# Puzzle_-_Temperature_Sensor_Analog_v1_0.net
KiCad netlist of a schematic drawn in EAGLE
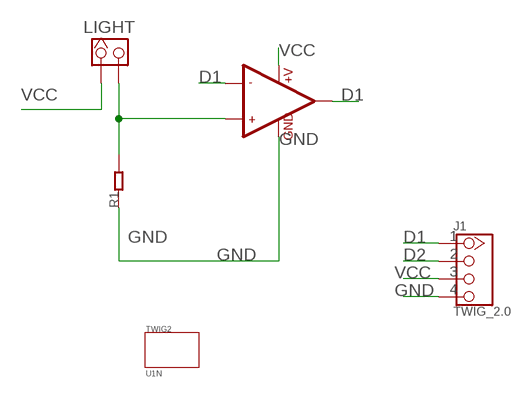
[diagram p0: schematic, sheet 1]

(export (version "E")
  (design (tool "Eeschema 10.0.6"))
  (components
    (comp (ref "J1")
      (value "TWIG_2.0")
      (footprint "eagle-import:2.0_1X4")
      (libsource (lib "eagle-import") (part "TWIG_2.0F''"))
    )
    (comp (ref "LIGHT")
      (value "HEADER_1X2_2.54")
      (footprint "eagle-import:CK_1_2")
      (libsource (lib "eagle-import") (part "HEADER_1X2_2.54"))
    )
    (comp (ref "R1")
      (value "R0603")
      (footprint "eagle-import:0603")
      (libsource (lib "eagle-import") (part "R0603"))
    )
    (comp (ref "TWIG2")
      (value "U1N")
      (footprint "eagle-import:U1N")
      (libsource (lib "eagle-import") (part "U1N"))
    )
    (comp (ref "U1")
      (value "LMV358")
      (footprint "eagle-import:SO08")
      (libsource (lib "eagle-import") (part "LMV358"))
    )
  )
  (nets
    (net (code "1") (name "/D1") (class "Default")
      (node (ref "J1") (pin "1") (pinfunction "1_1") (pintype "bidirectional"))
      (node (ref "U1") (pin "1") (pinfunction "OUT1_1") (pintype "output"))
      (node (ref "U1") (pin "2") (pinfunction "-IN1_2") (pintype "input"))
    )
    (net (code "2") (name "/D2") (class "Default")
      (node (ref "J1") (pin "2") (pinfunction "2_2") (pintype "bidirectional"))
    )
    (net (code "3") (name "/GND") (class "Default")
      (node (ref "J1") (pin "4") (pinfunction "4_4") (pintype "bidirectional"))
      (node (ref "R1") (pin "1") (pinfunction "1_1") (pintype "bidirectional"))
      (node (ref "U1") (pin "4") (pinfunction "GND_4") (pintype "power_in"))
    )
    (net (code "4") (name "/VCC") (class "Default")
      (node (ref "J1") (pin "3") (pinfunction "3_3") (pintype "bidirectional"))
      (node (ref "LIGHT") (pin "1") (pinfunction "1_1") (pintype "bidirectional"))
      (node (ref "U1") (pin "8") (pinfunction "+V_8") (pintype "power_in"))
    )
    (net (code "5") (name "Net-(U1A-+IN1)") (class "Default")
      (node (ref "LIGHT") (pin "2") (pinfunction "2_2") (pintype "bidirectional"))
      (node (ref "R1") (pin "2") (pinfunction "2_2") (pintype "bidirectional"))
      (node (ref "U1") (pin "3") (pinfunction "+IN1_3") (pintype "input"))
    )
  )
)
